# Activity_Recognition_Board_v1_0_Audio.net
KiCad netlist of a schematic drawn in Altium Designer
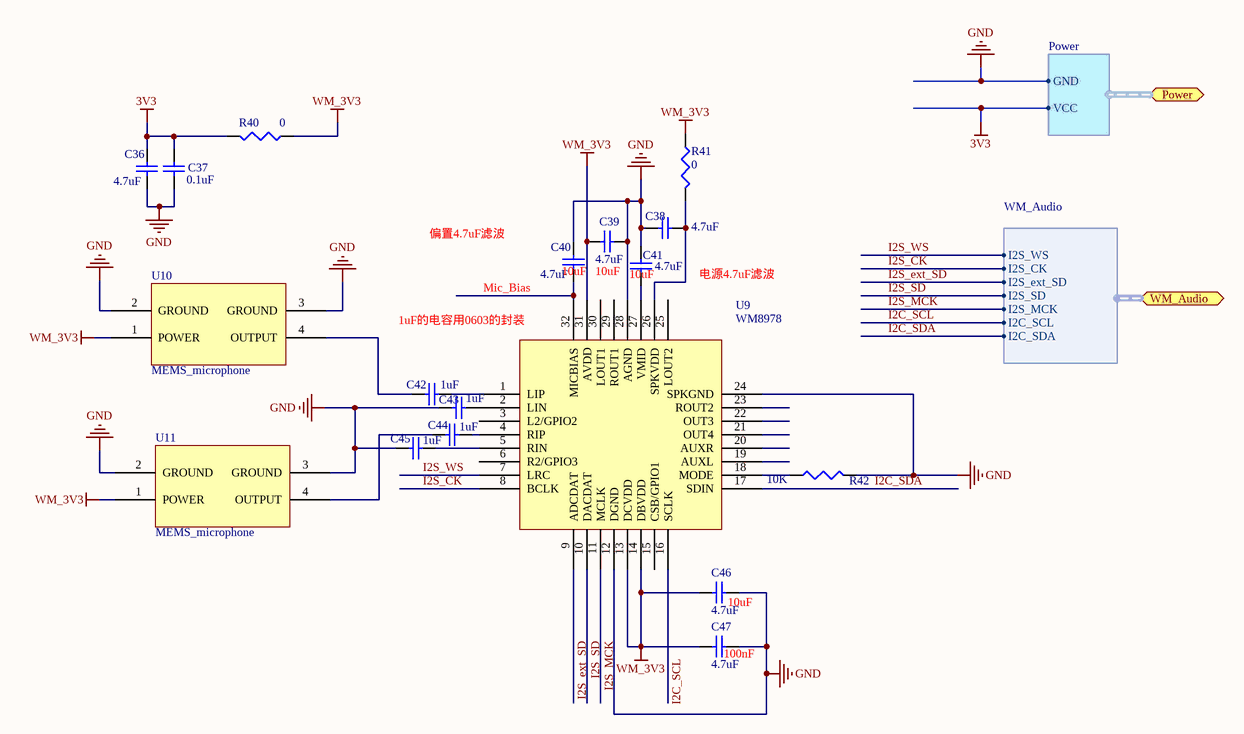
[diagram p0: Activity_Recognition_Board_v1.0_Audio.SchDoc]

(export (version "E")
  (design (tool "Eeschema 10.0.6"))
  (components
    (comp (ref "C36")
      (value "4.7uF")
      (footprint "C0603")
      (description "Capacitor (Semiconductor SIM Model)")
      (fields (field (name "Comment") "Cap semi") (field (name "PUBLISHER") "Altium Limited"))
      (libsource (lib "Miscellaneous Devices") (part "Cap Semi"))
    )
    (comp (ref "C37")
      (value "0.1uF")
      (footprint "C0402")
      (description "Capacitor (Semiconductor SIM Model)")
      (fields (field (name "Comment") "Cap semi") (field (name "PUBLISHER") "Altium Limited"))
      (libsource (lib "Miscellaneous Devices") (part "Cap Semi"))
    )
    (comp (ref "C38")
      (value "4.7uF")
      (footprint "C0603")
      (description "Capacitor (Semiconductor SIM Model)")
      (fields (field (name "Comment") "Cap semi") (field (name "PUBLISHER") "Altium Limited"))
      (libsource (lib "Miscellaneous Devices") (part "Cap Semi"))
    )
    (comp (ref "C39")
      (value "4.7uF")
      (footprint "C0603")
      (description "Capacitor (Semiconductor SIM Model)")
      (fields (field (name "Comment") "Cap semi") (field (name "PUBLISHER") "Altium Limited"))
      (libsource (lib "Miscellaneous Devices") (part "Cap Semi"))
    )
    (comp (ref "C40")
      (value "4.7uF")
      (footprint "C0603")
      (description "Capacitor (Semiconductor SIM Model)")
      (fields (field (name "Comment") "Cap semi") (field (name "PUBLISHER") "Altium Limited"))
      (libsource (lib "Miscellaneous Devices") (part "Cap Semi"))
    )
    (comp (ref "C41")
      (value "4.7uF")
      (footprint "C0603")
      (description "Capacitor (Semiconductor SIM Model)")
      (fields (field (name "Comment") "Cap semi") (field (name "PUBLISHER") "Altium Limited"))
      (libsource (lib "Miscellaneous Devices") (part "Cap Semi"))
    )
    (comp (ref "C42")
      (value "1uF")
      (footprint "C0603")
      (description "Capacitor (Semiconductor SIM Model)")
      (fields (field (name "Comment") "Cap semi") (field (name "PUBLISHER") "Altium Limited"))
      (libsource (lib "Miscellaneous Devices") (part "Cap Semi"))
    )
    (comp (ref "C43")
      (value "1uF")
      (footprint "C0603")
      (description "Capacitor (Semiconductor SIM Model)")
      (fields (field (name "Comment") "Cap semi") (field (name "PUBLISHER") "Altium Limited"))
      (libsource (lib "Miscellaneous Devices") (part "Cap Semi"))
    )
    (comp (ref "C44")
      (value "1uF")
      (footprint "C0603")
      (description "Capacitor (Semiconductor SIM Model)")
      (fields (field (name "Comment") "Cap semi") (field (name "PUBLISHER") "Altium Limited"))
      (libsource (lib "Miscellaneous Devices") (part "Cap Semi"))
    )
    (comp (ref "C45")
      (value "1uF")
      (footprint "C0603")
      (description "Capacitor (Semiconductor SIM Model)")
      (fields (field (name "Comment") "Cap semi") (field (name "PUBLISHER") "Altium Limited"))
      (libsource (lib "Miscellaneous Devices") (part "Cap Semi"))
    )
    (comp (ref "C46")
      (value "4.7uF")
      (footprint "C0603")
      (description "Capacitor (Semiconductor SIM Model)")
      (fields (field (name "Comment") "Cap semi") (field (name "PUBLISHER") "Altium Limited"))
      (libsource (lib "Miscellaneous Devices") (part "Cap Semi"))
    )
    (comp (ref "C47")
      (value "4.7uF")
      (footprint "C0603")
      (description "Capacitor (Semiconductor SIM Model)")
      (fields (field (name "Comment") "Cap semi") (field (name "PUBLISHER") "Altium Limited"))
      (libsource (lib "Miscellaneous Devices") (part "Cap Semi"))
    )
    (comp (ref "R40")
      (value "0")
      (footprint "R0603")
      (description "Resistor")
      (fields (field (name "Comment") "Res3") (field (name "PUBLISHER") "Altium Limited"))
      (libsource (lib "Miscellaneous Devices") (part "Res3"))
    )
    (comp (ref "R41")
      (value "0")
      (footprint "R0402")
      (description "Resistor")
      (fields (field (name "Comment") "Res3") (field (name "PUBLISHER") "Altium Limited"))
      (libsource (lib "Miscellaneous Devices") (part "Res3"))
    )
    (comp (ref "R42")
      (value "10K")
      (footprint "R0402")
      (description "Resistor")
      (fields (field (name "Comment") "Res3") (field (name "PUBLISHER") "Altium Limited"))
      (libsource (lib "Miscellaneous Devices") (part "Res3"))
    )
    (comp (ref "U9")
      (value "WM8978")
      (footprint "QFN32")
      (libsource (lib "Activity_Recognition_Board") (part "WM8978"))
    )
    (comp (ref "U10")
      (value "MEMS_microphone")
      (footprint "Microphone")
      (libsource (lib "Activity_Recognition_Board") (part "MEMS_microphone"))
    )
    (comp (ref "U11")
      (value "MEMS_microphone")
      (footprint "Microphone")
      (libsource (lib "Activity_Recognition_Board") (part "MEMS_microphone"))
    )
  )
  (nets
    (net (code "4") (name "/I2C_SCL") (class "Default")
      (node (ref "U9") (pin "16") (pinfunction "SCLK_16") (pintype "passive"))
    )
    (net (code "5") (name "/I2C_SDA") (class "Default")
      (node (ref "U9") (pin "17") (pinfunction "SDIN_17") (pintype "passive"))
    )
    (net (code "6") (name "/I2S_CK") (class "Default")
      (node (ref "U9") (pin "8") (pinfunction "BCLK_8") (pintype "passive"))
    )
    (net (code "7") (name "/I2S_MCK") (class "Default")
      (node (ref "U9") (pin "11") (pinfunction "MCLK_11") (pintype "passive"))
    )
    (net (code "8") (name "/I2S_SD") (class "Default")
      (node (ref "U9") (pin "10") (pinfunction "DACDAT_10") (pintype "passive"))
    )
    (net (code "9") (name "/I2S_WS") (class "Default")
      (node (ref "U9") (pin "7") (pinfunction "LRC_7") (pintype "passive"))
    )
    (net (code "10") (name "/I2S_ext_SD") (class "Default")
      (node (ref "U9") (pin "9") (pinfunction "ADCDAT_9") (pintype "passive"))
    )
    (net (code "11") (name "/Mic_Bias") (class "Default")
      (node (ref "C40") (pin "2") (pinfunction "2_2") (pintype "passive"))
      (node (ref "U9") (pin "32") (pinfunction "MICBIAS_32") (pintype "passive"))
    )
    (net (code "16") (name "3V3") (class "Default")
      (node (ref "C36") (pin "1") (pinfunction "1_1") (pintype "passive"))
      (node (ref "C37") (pin "1") (pinfunction "1_1") (pintype "passive"))
      (node (ref "R40") (pin "2") (pinfunction "2_2") (pintype "passive"))
    )
    (net (code "17") (name "GND") (class "Default")
      (node (ref "C36") (pin "2") (pinfunction "2_2") (pintype "passive"))
      (node (ref "C37") (pin "2") (pinfunction "2_2") (pintype "passive"))
      (node (ref "C38") (pin "1") (pinfunction "1_1") (pintype "passive"))
      (node (ref "C39") (pin "2") (pinfunction "2_2") (pintype "passive"))
      (node (ref "C40") (pin "1") (pinfunction "1_1") (pintype "passive"))
      (node (ref "C41") (pin "1") (pinfunction "1_1") (pintype "passive"))
      (node (ref "C43") (pin "2") (pinfunction "2_2") (pintype "passive"))
      (node (ref "C45") (pin "2") (pinfunction "2_2") (pintype "passive"))
      (node (ref "C46") (pin "2") (pinfunction "2_2") (pintype "passive"))
      (node (ref "C47") (pin "2") (pinfunction "2_2") (pintype "passive"))
      (node (ref "R42") (pin "2") (pinfunction "2_2") (pintype "passive"))
      (node (ref "U10") (pin "2") (pinfunction "GROUND_2") (pintype "passive"))
      (node (ref "U10") (pin "3") (pinfunction "GROUND_3") (pintype "passive"))
      (node (ref "U11") (pin "2") (pinfunction "GROUND_2") (pintype "passive"))
      (node (ref "U11") (pin "3") (pinfunction "GROUND_3") (pintype "passive"))
      (node (ref "U9") (pin "12") (pinfunction "DGND_12") (pintype "passive"))
      (node (ref "U9") (pin "24") (pinfunction "SPKGND_24") (pintype "passive"))
      (node (ref "U9") (pin "28") (pinfunction "AGND_28") (pintype "passive"))
    )
    (net (code "18") (name "Net-(U9-LIN)") (class "Default")
      (node (ref "C43") (pin "1") (pinfunction "1_1") (pintype "passive"))
      (node (ref "U9") (pin "2") (pinfunction "LIN_2") (pintype "passive"))
    )
    (net (code "19") (name "Net-(U9-LIP)") (class "Default")
      (node (ref "C42") (pin "1") (pinfunction "1_1") (pintype "passive"))
      (node (ref "U9") (pin "1") (pinfunction "LIP_1") (pintype "passive"))
    )
    (net (code "20") (name "Net-(U9-MODE)") (class "Default")
      (node (ref "R42") (pin "1") (pinfunction "1_1") (pintype "passive"))
      (node (ref "U9") (pin "18") (pinfunction "MODE_18") (pintype "passive"))
    )
    (net (code "21") (name "Net-(U9-RIN)") (class "Default")
      (node (ref "C45") (pin "1") (pinfunction "1_1") (pintype "passive"))
      (node (ref "U9") (pin "5") (pinfunction "RIN_5") (pintype "passive"))
    )
    (net (code "22") (name "Net-(U9-RIP)") (class "Default")
      (node (ref "C44") (pin "1") (pinfunction "1_1") (pintype "passive"))
      (node (ref "U9") (pin "4") (pinfunction "RIP_4") (pintype "passive"))
    )
    (net (code "23") (name "Net-(U9-SPKVDD)") (class "Default")
      (node (ref "C38") (pin "2") (pinfunction "2_2") (pintype "passive"))
      (node (ref "R41") (pin "2") (pinfunction "2_2") (pintype "passive"))
      (node (ref "U9") (pin "26") (pinfunction "SPKVDD_26") (pintype "passive"))
    )
    (net (code "24") (name "Net-(U9-VMID)") (class "Default")
      (node (ref "C41") (pin "2") (pinfunction "2_2") (pintype "passive"))
      (node (ref "U9") (pin "27") (pinfunction "VMID_27") (pintype "passive"))
    )
    (net (code "25") (name "Net-(U10-OUTPUT)") (class "Default")
      (node (ref "C42") (pin "2") (pinfunction "2_2") (pintype "passive"))
      (node (ref "U10") (pin "4") (pinfunction "OUTPUT_4") (pintype "passive"))
    )
    (net (code "26") (name "Net-(U11-OUTPUT)") (class "Default")
      (node (ref "C44") (pin "2") (pinfunction "2_2") (pintype "passive"))
      (node (ref "U11") (pin "4") (pinfunction "OUTPUT_4") (pintype "passive"))
    )
    (net (code "27") (name "WM_3V3") (class "Default")
      (node (ref "C39") (pin "1") (pinfunction "1_1") (pintype "passive"))
      (node (ref "C46") (pin "1") (pinfunction "1_1") (pintype "passive"))
      (node (ref "C47") (pin "1") (pinfunction "1_1") (pintype "passive"))
      (node (ref "R40") (pin "1") (pinfunction "1_1") (pintype "passive"))
      (node (ref "R41") (pin "1") (pinfunction "1_1") (pintype "passive"))
      (node (ref "U10") (pin "1") (pinfunction "POWER_1") (pintype "passive"))
      (node (ref "U11") (pin "1") (pinfunction "POWER_1") (pintype "passive"))
      (node (ref "U9") (pin "13") (pinfunction "DCVDD_13") (pintype "passive"))
      (node (ref "U9") (pin "14") (pinfunction "DBVDD_14") (pintype "passive"))
      (node (ref "U9") (pin "31") (pinfunction "AVDD_31") (pintype "passive"))
    )
    (net (code "28") (name "unconnected-(U9-AUXL-Pad19)") (class "Default")
      (node (ref "U9") (pin "19") (pinfunction "AUXL_19") (pintype "passive"))
    )
    (net (code "29") (name "unconnected-(U9-AUXR-Pad20)") (class "Default")
      (node (ref "U9") (pin "20") (pinfunction "AUXR_20") (pintype "passive"))
    )
    (net (code "30") (name "unconnected-(U9-CSB{slash}GPIO1-Pad15)") (class "Default")
      (node (ref "U9") (pin "15") (pinfunction "CSB/GPIO1_15") (pintype "passive"))
    )
    (net (code "31") (name "unconnected-(U9-L2{slash}GPIO2-Pad3)") (class "Default")
      (node (ref "U9") (pin "3") (pinfunction "L2/GPIO2_3") (pintype "passive"))
    )
    (net (code "32") (name "unconnected-(U9-LOUT1-Pad30)") (class "Default")
      (node (ref "U9") (pin "30") (pinfunction "LOUT1_30") (pintype "passive"))
    )
    (net (code "33") (name "unconnected-(U9-LOUT2-Pad25)") (class "Default")
      (node (ref "U9") (pin "25") (pinfunction "LOUT2_25") (pintype "passive"))
    )
    (net (code "34") (name "unconnected-(U9-OUT3-Pad22)") (class "Default")
      (node (ref "U9") (pin "22") (pinfunction "OUT3_22") (pintype "passive"))
    )
    (net (code "35") (name "unconnected-(U9-OUT4-Pad21)") (class "Default")
      (node (ref "U9") (pin "21") (pinfunction "OUT4_21") (pintype "passive"))
    )
    (net (code "36") (name "unconnected-(U9-R2{slash}GPIO3-Pad6)") (class "Default")
      (node (ref "U9") (pin "6") (pinfunction "R2/GPIO3_6") (pintype "passive"))
    )
    (net (code "37") (name "unconnected-(U9-ROUT1-Pad29)") (class "Default")
      (node (ref "U9") (pin "29") (pinfunction "ROUT1_29") (pintype "passive"))
    )
    (net (code "38") (name "unconnected-(U9-ROUT2-Pad23)") (class "Default")
      (node (ref "U9") (pin "23") (pinfunction "ROUT2_23") (pintype "passive"))
    )
  )
)
